# POWER.net
KiCad netlist of a schematic drawn in Altium Designer
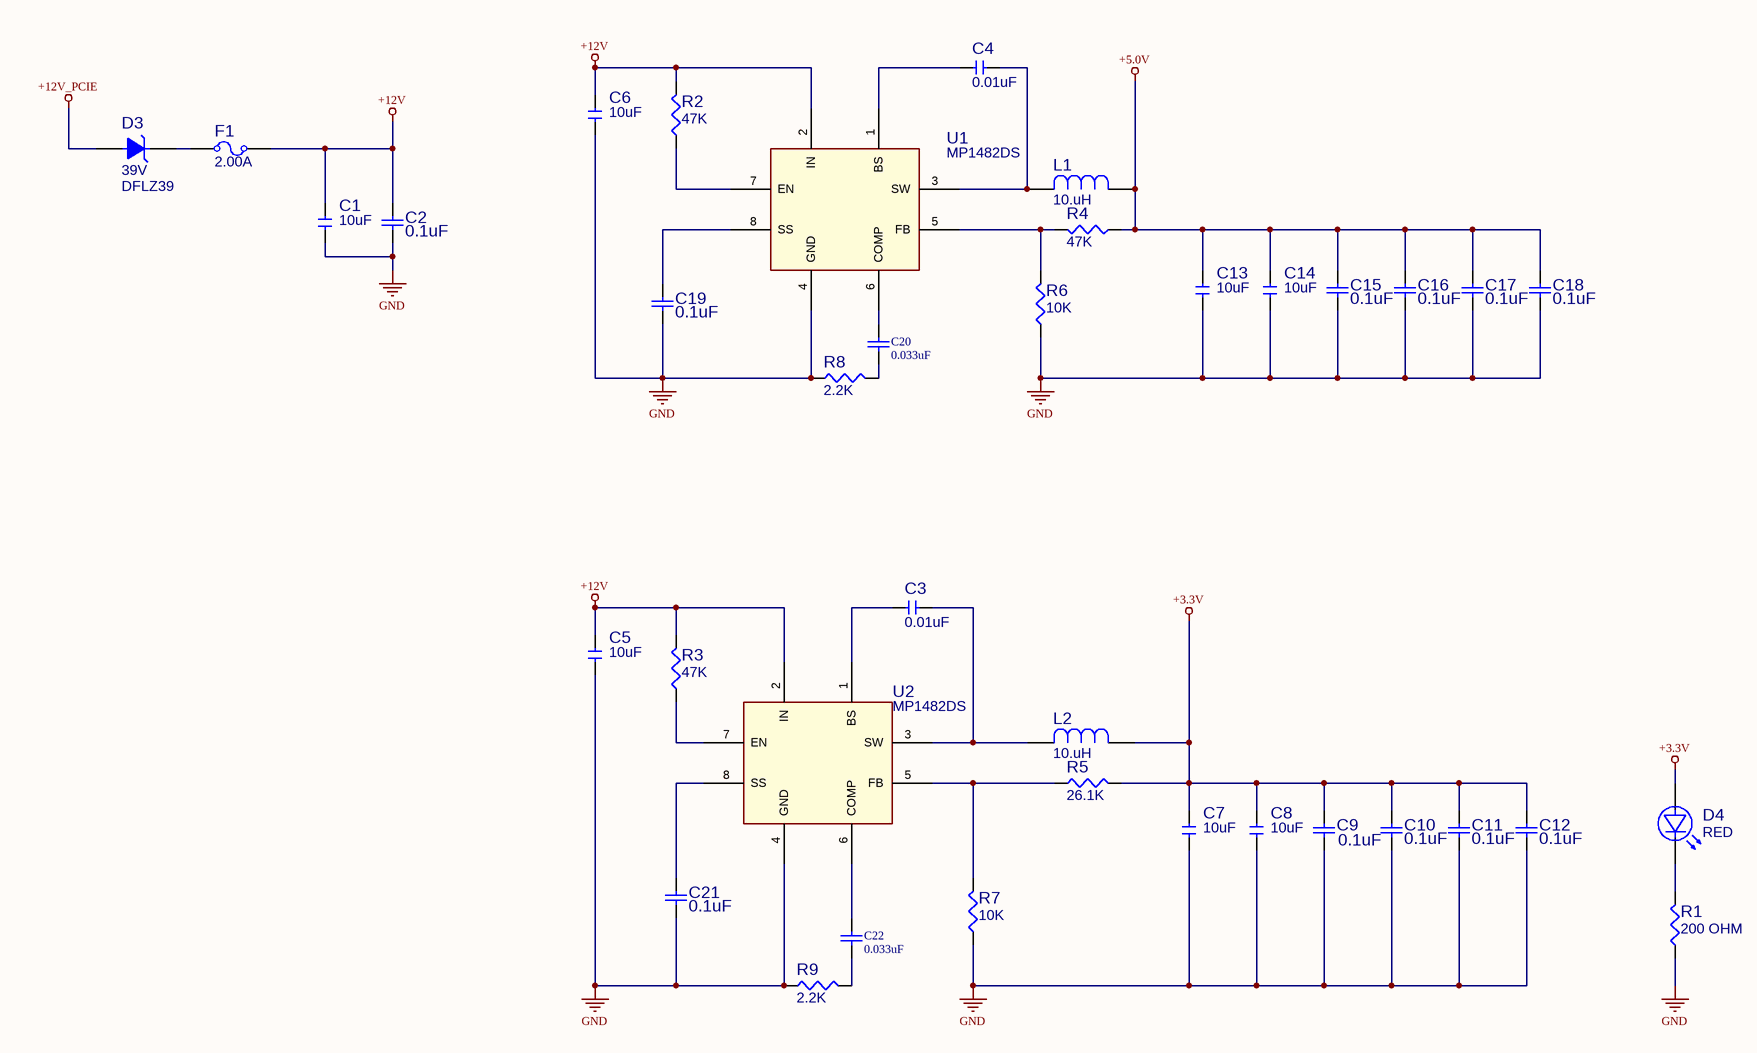
[diagram p0: POWER.SchDoc]

(export (version "E")
  (design (tool "Eeschema 10.0.6"))
  (components
    (comp (ref "C1")
      (value "10uF")
      (footprint "CAPC2012X14N")
      (description "CAP, CER, 10.UF, 25V, 10%, X5R, 0805")
      (fields
        (field (name "MFG PART NUM") "TMK212BBJ106KG-T")
        (field (name "VALENTIUM PART NUM") "<VALENTIUM>")
      )
      (libsource (lib "Capacitors") (part "CAP_0805_10UF_25V"))
    )
    (comp (ref "C2")
      (value "0.1uF")
      (footprint "CAPC1608X87X45ML20T05")
      (description "C0603X104K5RACAUTO")
      (fields (field (name "MANUFACTURER") "Kemet"))
      (libsource (lib "Altium Content Vault") (part "CAP"))
    )
    (comp (ref "C3")
      (value "0.01uF")
      (footprint "CAPC1608X10N")
      (description "CAP, CER, 0.01UF, 50V, 10%, X7R, 0603")
      (fields
        (field (name "MFG PART NUM") "C0603C103K5RACTU")
        (field (name "VALENTIUM PART NUM") "<VALENTIUM>")
      )
      (libsource (lib "Capacitors") (part "CAP_0603_0.01UF_50V"))
    )
    (comp (ref "C4")
      (value "0.01uF")
      (footprint "CAPC1608X10N")
      (description "CAP, CER, 0.01UF, 50V, 10%, X7R, 0603")
      (fields
        (field (name "MFG PART NUM") "C0603C103K5RACTU")
        (field (name "VALENTIUM PART NUM") "<VALENTIUM>")
      )
      (libsource (lib "Capacitors") (part "CAP_0603_0.01UF_50V"))
    )
    (comp (ref "C5")
      (value "10uF")
      (footprint "CAPC2012X14N")
      (description "CAP, CER, 10.UF, 25V, 10%, X5R, 0805")
      (fields
        (field (name "MFG PART NUM") "TMK212BBJ106KG-T")
        (field (name "VALENTIUM PART NUM") "<VALENTIUM>")
      )
      (libsource (lib "Capacitors") (part "CAP_0805_10UF_25V"))
    )
    (comp (ref "C6")
      (value "10uF")
      (footprint "CAPC2012X14N")
      (description "CAP, CER, 10.UF, 25V, 10%, X5R, 0805")
      (fields
        (field (name "MFG PART NUM") "TMK212BBJ106KG-T")
        (field (name "VALENTIUM PART NUM") "<VALENTIUM>")
      )
      (libsource (lib "Capacitors") (part "CAP_0805_10UF_25V"))
    )
    (comp (ref "C7")
      (value "10uF")
      (footprint "CAPC2012X14N")
      (description "CAP, CER, 10.UF, 25V, 10%, X5R, 0805")
      (fields
        (field (name "MFG PART NUM") "TMK212BBJ106KG-T")
        (field (name "VALENTIUM PART NUM") "<VALENTIUM>")
      )
      (libsource (lib "Capacitors") (part "CAP_0805_10UF_25V"))
    )
    (comp (ref "C8")
      (value "10uF")
      (footprint "CAPC2012X14N")
      (description "CAP, CER, 10.UF, 25V, 10%, X5R, 0805")
      (fields
        (field (name "MFG PART NUM") "TMK212BBJ106KG-T")
        (field (name "VALENTIUM PART NUM") "<VALENTIUM>")
      )
      (libsource (lib "Capacitors") (part "CAP_0805_10UF_25V"))
    )
    (comp (ref "C9")
      (value "0.1uF")
      (footprint "CAPC1608X87X45ML20T05")
      (description "C0603X104K5RACAUTO")
      (fields (field (name "MANUFACTURER") "Kemet"))
      (libsource (lib "Altium Content Vault") (part "CAP"))
    )
    (comp (ref "C10")
      (value "0.1uF")
      (footprint "CAPC1608X87X45ML20T05")
      (description "C0603X104K5RACAUTO")
      (fields (field (name "MANUFACTURER") "Kemet"))
      (libsource (lib "Altium Content Vault") (part "CAP"))
    )
    (comp (ref "C11")
      (value "0.1uF")
      (footprint "CAPC1608X87X45ML20T05")
      (description "C0603X104K5RACAUTO")
      (fields (field (name "MANUFACTURER") "Kemet"))
      (libsource (lib "Altium Content Vault") (part "CAP"))
    )
    (comp (ref "C12")
      (value "0.1uF")
      (footprint "CAPC1608X87X45ML20T05")
      (description "C0603X104K5RACAUTO")
      (fields (field (name "MANUFACTURER") "Kemet"))
      (libsource (lib "Altium Content Vault") (part "CAP"))
    )
    (comp (ref "C13")
      (value "10uF")
      (footprint "CAPC2012X14N")
      (description "CAP, CER, 10.UF, 25V, 10%, X5R, 0805")
      (fields
        (field (name "MFG PART NUM") "TMK212BBJ106KG-T")
        (field (name "VALENTIUM PART NUM") "<VALENTIUM>")
      )
      (libsource (lib "Capacitors") (part "CAP_0805_10UF_25V"))
    )
    (comp (ref "C14")
      (value "10uF")
      (footprint "CAPC2012X14N")
      (description "CAP, CER, 10.UF, 25V, 10%, X5R, 0805")
      (fields
        (field (name "MFG PART NUM") "TMK212BBJ106KG-T")
        (field (name "VALENTIUM PART NUM") "<VALENTIUM>")
      )
      (libsource (lib "Capacitors") (part "CAP_0805_10UF_25V"))
    )
    (comp (ref "C15")
      (value "0.1uF")
      (footprint "CAPC1608X87X45ML20T05")
      (description "C0603X104K5RACAUTO")
      (fields (field (name "MANUFACTURER") "Kemet"))
      (libsource (lib "Altium Content Vault") (part "CAP"))
    )
    (comp (ref "C16")
      (value "0.1uF")
      (footprint "CAPC1608X87X45ML20T05")
      (description "C0603X104K5RACAUTO")
      (fields (field (name "MANUFACTURER") "Kemet"))
      (libsource (lib "Altium Content Vault") (part "CAP"))
    )
    (comp (ref "C17")
      (value "0.1uF")
      (footprint "CAPC1608X87X45ML20T05")
      (description "C0603X104K5RACAUTO")
      (fields (field (name "MANUFACTURER") "Kemet"))
      (libsource (lib "Altium Content Vault") (part "CAP"))
    )
    (comp (ref "C18")
      (value "0.1uF")
      (footprint "CAPC1608X87X45ML20T05")
      (description "C0603X104K5RACAUTO")
      (fields (field (name "MANUFACTURER") "Kemet"))
      (libsource (lib "Altium Content Vault") (part "CAP"))
    )
    (comp (ref "C19")
      (value "0.1uF")
      (footprint "CAPC1608X87X45ML20T05")
      (description "C0603X104K5RACAUTO")
      (fields (field (name "MANUFACTURER") "Kemet"))
      (libsource (lib "Altium Content Vault") (part "CAP"))
    )
    (comp (ref "C20")
      (value "0.033uF")
      (footprint "CAPC1608X90X35NL10T15")
      (description "GCM188R71H333KA55D")
      (fields (field (name "MANUFACTURER") "Murata"))
      (libsource (lib "Altium Content Vault") (part "CAP"))
    )
    (comp (ref "C21")
      (value "0.1uF")
      (footprint "CAPC1608X87X45ML20T05")
      (description "C0603X104K5RACAUTO")
      (fields (field (name "MANUFACTURER") "Kemet"))
      (libsource (lib "Altium Content Vault") (part "CAP"))
    )
    (comp (ref "C22")
      (value "0.033uF")
      (footprint "CAPC1608X90X35NL10T15")
      (description "GCM188R71H333KA55D")
      (fields (field (name "MANUFACTURER") "Murata"))
      (libsource (lib "Altium Content Vault") (part "CAP"))
    )
    (comp (ref "D3")
      (value "DFLZ39")
      (footprint "SODFL370X135-2N")
      (description "DIO, ZENER, DFLZ39, 39V, 5%, 1W, SOD123FL")
      (fields
        (field (name "MFG PART NUM") "DFLZ39-TP")
        (field (name "P1") "39V")
        (field (name "VALENTIUM PART NUM") "<VALENTIUM>")
      )
      (libsource (lib "Passives") (part "DFLZ39"))
    )
    (comp (ref "D4")
      (value "RED")
      (footprint "DIOM1608X06N")
      (description "LED, RED, SML-LX0603, 635NM, 2V, 20MA, 0603")
      (fields
        (field (name "MFG PART NUM") "SML-LX0603IW-TR")
        (field (name "VALENTIUM PART NUM") "<VALENTIUM>")
      )
      (libsource (lib "Passives") (part "SMTLED_RED_0603_SML"))
    )
    (comp (ref "F1")
      (value "2.00A")
      (footprint "FUSM1608X60N")
      (description "FUSE SLOW 2.00A 32V M 0603")
      (fields (field (name "MFG PART NUM") "SF-0603S200-2") (field (name "VALENTIUM PART NUM") "<VALENTIUM>"))
      (libsource (lib "Passives") (part "FUSE_0603_2.00A"))
    )
    (comp (ref "L1")
      (value "10.uH")
      (footprint "IND_PM124SH")
      (description "IND, PWR, 10.uH, 20%, 4A, 0.04DCR, 12.5X12.5MM, SHLD")
      (fields
        (field (name "MFG PART NUM") "PM124SH-100M-RC")
        (field (name "VALENTIUM PART NUM") "<VALENTIUM>")
      )
      (libsource (lib "Passives") (part "PM124SH-100M-RC"))
    )
    (comp (ref "L2")
      (value "10.uH")
      (footprint "IND_PM124SH")
      (description "IND, PWR, 10.uH, 20%, 4A, 0.04DCR, 12.5X12.5MM, SHLD")
      (fields
        (field (name "MFG PART NUM") "PM124SH-100M-RC")
        (field (name "VALENTIUM PART NUM") "<VALENTIUM>")
      )
      (libsource (lib "Passives") (part "PM124SH-100M-RC"))
    )
    (comp (ref "R1")
      (value "200 OHM")
      (footprint "RESC1608X50N")
      (description "RES, 200 OHM, 1%, 1/10W, TF, 0603")
      (fields (field (name "MFG PART NUM") "ERJ-3EKF2000V") (field (name "VELENTIUM PART NUM") "<VELENTIUM>"))
      (libsource (lib "Resistors") (part "RES_0603_200"))
    )
    (comp (ref "R2")
      (value "47K")
      (footprint "RESC1608X50N")
      (description "RES, 47K, 1%, 1/10W, TF, 0603")
      (fields (field (name "MFG PART NUM") "ERJ-3EKF4702V") (field (name "VELENTIUM PART NUM") "<VELENTIUM>"))
      (libsource (lib "Resistors") (part "RES_0603_47K"))
    )
    (comp (ref "R3")
      (value "47K")
      (footprint "RESC1608X50N")
      (description "RES, 47K, 1%, 1/10W, TF, 0603")
      (fields (field (name "MFG PART NUM") "ERJ-3EKF4702V") (field (name "VELENTIUM PART NUM") "<VELENTIUM>"))
      (libsource (lib "Resistors") (part "RES_0603_47K"))
    )
    (comp (ref "R4")
      (value "47K")
      (footprint "RESC1608X50N")
      (description "RES, 47K, 1%, 1/10W, TF, 0603")
      (fields (field (name "MFG PART NUM") "ERJ-3EKF4702V") (field (name "VELENTIUM PART NUM") "<VELENTIUM>"))
      (libsource (lib "Resistors") (part "RES_0603_47K"))
    )
    (comp (ref "R5")
      (value "26.1K")
      (footprint "RESC1608X50N")
      (description "RES, 26.1K, 1%, 1/10W, TF, 0603")
      (fields (field (name "MFG PART NUM") "ERJ-3EKF2612V") (field (name "VELENTIUM PART NUM") "<VELENTIUM>"))
      (libsource (lib "Resistors") (part "RES_0603_26.1K"))
    )
    (comp (ref "R6")
      (value "10K")
      (footprint "RESC1608X50N")
      (description "RES, 10K, 1%, 1/10W, TF, 0603")
      (fields (field (name "MFG PART NUM") "ERJ-3EKF1002V") (field (name "VELENTIUM PART NUM") "<VELENTIUM>"))
      (libsource (lib "Resistors") (part "RES_0603_10K"))
    )
    (comp (ref "R7")
      (value "10K")
      (footprint "RESC1608X50N")
      (description "RES, 10K, 1%, 1/10W, TF, 0603")
      (fields (field (name "MFG PART NUM") "ERJ-3EKF1002V") (field (name "VELENTIUM PART NUM") "<VELENTIUM>"))
      (libsource (lib "Resistors") (part "RES_0603_10K"))
    )
    (comp (ref "R8")
      (value "2.2K")
      (footprint "RESC1608X50N")
      (description "RES, 2.2K, 1%, 1/10W, TF, 0603")
      (fields (field (name "MFG PART NUM") "ERJ-3EKF2201V") (field (name "VELENTIUM PART NUM") "<VELENTIUM>"))
      (libsource (lib "Resistors") (part "RES_0603_2.2K"))
    )
    (comp (ref "R9")
      (value "2.2K")
      (footprint "RESC1608X50N")
      (description "RES, 2.2K, 1%, 1/10W, TF, 0603")
      (fields (field (name "MFG PART NUM") "ERJ-3EKF2201V") (field (name "VELENTIUM PART NUM") "<VELENTIUM>"))
      (libsource (lib "Resistors") (part "RES_0603_2.2K"))
    )
    (comp (ref "U1")
      (value "MP1482DS")
      (footprint "SOIC127P600X175-8N")
      (description "IC, DC/DC, MP1482DS, >4.75VIN, 0.923-15V OUT, SOIC8")
      (fields (field (name "MFG PART NUM") "MP1482DS-LF") (field (name "VELENTIUM PART NUM") "<V PART NUM>"))
      (libsource (lib "IntegratedCircuits") (part "MP1482DS"))
    )
    (comp (ref "U2")
      (value "MP1482DS")
      (footprint "SOIC127P600X175-8N")
      (description "IC, DC/DC, MP1482DS, >4.75VIN, 0.923-15V OUT, SOIC8")
      (fields (field (name "MFG PART NUM") "MP1482DS-LF") (field (name "VELENTIUM PART NUM") "<V PART NUM>"))
      (libsource (lib "IntegratedCircuits") (part "MP1482DS"))
    )
  )
  (nets
    (net (code "1") (name "+3.3V") (class "Default")
      (node (ref "C10") (pin "2") (pinfunction "2_2") (pintype "passive"))
      (node (ref "C11") (pin "2") (pinfunction "2_2") (pintype "passive"))
      (node (ref "C12") (pin "2") (pinfunction "2_2") (pintype "passive"))
      (node (ref "C7") (pin "1") (pinfunction "1_1") (pintype "passive"))
      (node (ref "C8") (pin "1") (pinfunction "1_1") (pintype "passive"))
      (node (ref "C9") (pin "2") (pinfunction "2_2") (pintype "passive"))
      (node (ref "D4") (pin "2") (pinfunction "A_2") (pintype "passive"))
      (node (ref "L2") (pin "1") (pintype "passive"))
      (node (ref "R5") (pin "2") (pinfunction "2_2") (pintype "passive"))
    )
    (net (code "2") (name "+5.0V") (class "Default")
      (node (ref "C13") (pin "1") (pinfunction "1_1") (pintype "passive"))
      (node (ref "C14") (pin "1") (pinfunction "1_1") (pintype "passive"))
      (node (ref "C15") (pin "2") (pinfunction "2_2") (pintype "passive"))
      (node (ref "C16") (pin "2") (pinfunction "2_2") (pintype "passive"))
      (node (ref "C17") (pin "2") (pinfunction "2_2") (pintype "passive"))
      (node (ref "C18") (pin "2") (pinfunction "2_2") (pintype "passive"))
      (node (ref "L1") (pin "1") (pintype "passive"))
      (node (ref "R4") (pin "1") (pinfunction "1_1") (pintype "passive"))
    )
    (net (code "3") (name "+12V") (class "Default")
      (node (ref "C1") (pin "1") (pinfunction "1_1") (pintype "passive"))
      (node (ref "C2") (pin "2") (pinfunction "2_2") (pintype "passive"))
      (node (ref "C5") (pin "1") (pinfunction "1_1") (pintype "passive"))
      (node (ref "C6") (pin "1") (pinfunction "1_1") (pintype "passive"))
      (node (ref "F1") (pin "2") (pinfunction "2_2") (pintype "passive"))
      (node (ref "R2") (pin "2") (pinfunction "2_2") (pintype "passive"))
      (node (ref "R3") (pin "2") (pinfunction "2_2") (pintype "passive"))
      (node (ref "U1") (pin "2") (pinfunction "IN_2") (pintype "passive"))
      (node (ref "U2") (pin "2") (pinfunction "IN_2") (pintype "passive"))
    )
    (net (code "4") (name "+12V_PCIE") (class "Default")
      (node (ref "D3") (pin "2") (pinfunction "A_2") (pintype "passive"))
    )
    (net (code "5") (name "GND") (class "Default")
      (node (ref "C1") (pin "2") (pinfunction "2_2") (pintype "passive"))
      (node (ref "C10") (pin "1") (pinfunction "1_1") (pintype "passive"))
      (node (ref "C11") (pin "1") (pinfunction "1_1") (pintype "passive"))
      (node (ref "C12") (pin "1") (pinfunction "1_1") (pintype "passive"))
      (node (ref "C13") (pin "2") (pinfunction "2_2") (pintype "passive"))
      (node (ref "C14") (pin "2") (pinfunction "2_2") (pintype "passive"))
      (node (ref "C15") (pin "1") (pinfunction "1_1") (pintype "passive"))
      (node (ref "C16") (pin "1") (pinfunction "1_1") (pintype "passive"))
      (node (ref "C17") (pin "1") (pinfunction "1_1") (pintype "passive"))
      (node (ref "C18") (pin "1") (pinfunction "1_1") (pintype "passive"))
      (node (ref "C19") (pin "1") (pinfunction "1_1") (pintype "passive"))
      (node (ref "C2") (pin "1") (pinfunction "1_1") (pintype "passive"))
      (node (ref "C21") (pin "1") (pinfunction "1_1") (pintype "passive"))
      (node (ref "C5") (pin "2") (pinfunction "2_2") (pintype "passive"))
      (node (ref "C6") (pin "2") (pinfunction "2_2") (pintype "passive"))
      (node (ref "C7") (pin "2") (pinfunction "2_2") (pintype "passive"))
      (node (ref "C8") (pin "2") (pinfunction "2_2") (pintype "passive"))
      (node (ref "C9") (pin "1") (pinfunction "1_1") (pintype "passive"))
      (node (ref "R1") (pin "1") (pinfunction "1_1") (pintype "passive"))
      (node (ref "R6") (pin "1") (pinfunction "1_1") (pintype "passive"))
      (node (ref "R7") (pin "1") (pinfunction "1_1") (pintype "passive"))
      (node (ref "R8") (pin "1") (pinfunction "1_1") (pintype "passive"))
      (node (ref "R9") (pin "1") (pinfunction "1_1") (pintype "passive"))
      (node (ref "U1") (pin "4") (pinfunction "GND_4") (pintype "passive"))
      (node (ref "U2") (pin "4") (pinfunction "GND_4") (pintype "passive"))
    )
    (net (code "6") (name "Net-(C20-Pad1)") (class "Default")
      (node (ref "C20") (pin "1") (pinfunction "1_1") (pintype "passive"))
      (node (ref "R8") (pin "2") (pinfunction "2_2") (pintype "passive"))
    )
    (net (code "7") (name "Net-(C22-Pad1)") (class "Default")
      (node (ref "C22") (pin "1") (pinfunction "1_1") (pintype "passive"))
      (node (ref "R9") (pin "2") (pinfunction "2_2") (pintype "passive"))
    )
    (net (code "8") (name "Net-(D3-C)") (class "Default")
      (node (ref "D3") (pin "1") (pinfunction "C_1") (pintype "passive"))
      (node (ref "F1") (pin "1") (pinfunction "1_1") (pintype "passive"))
    )
    (net (code "9") (name "Net-(D4-K)") (class "Default")
      (node (ref "D4") (pin "1") (pinfunction "K_1") (pintype "passive"))
      (node (ref "R1") (pin "2") (pinfunction "2_2") (pintype "passive"))
    )
    (net (code "10") (name "Net-(U1-BS)") (class "Default")
      (node (ref "C4") (pin "1") (pinfunction "1_1") (pintype "passive"))
      (node (ref "U1") (pin "1") (pinfunction "BS_1") (pintype "passive"))
    )
    (net (code "11") (name "Net-(U1-COMP)") (class "Default")
      (node (ref "C20") (pin "2") (pinfunction "2_2") (pintype "passive"))
      (node (ref "U1") (pin "6") (pinfunction "COMP_6") (pintype "passive"))
    )
    (net (code "12") (name "Net-(U1-EN)") (class "Default")
      (node (ref "R2") (pin "1") (pinfunction "1_1") (pintype "passive"))
      (node (ref "U1") (pin "7") (pinfunction "EN_7") (pintype "passive"))
    )
    (net (code "13") (name "Net-(U1-FB)") (class "Default")
      (node (ref "R4") (pin "2") (pinfunction "2_2") (pintype "passive"))
      (node (ref "R6") (pin "2") (pinfunction "2_2") (pintype "passive"))
      (node (ref "U1") (pin "5") (pinfunction "FB_5") (pintype "passive"))
    )
    (net (code "14") (name "Net-(U1-SS)") (class "Default")
      (node (ref "C19") (pin "2") (pinfunction "2_2") (pintype "passive"))
      (node (ref "U1") (pin "8") (pinfunction "SS_8") (pintype "passive"))
    )
    (net (code "15") (name "Net-(U1-SW)") (class "Default")
      (node (ref "C4") (pin "2") (pinfunction "2_2") (pintype "passive"))
      (node (ref "L1") (pin "2") (pintype "passive"))
      (node (ref "U1") (pin "3") (pinfunction "SW_3") (pintype "passive"))
    )
    (net (code "16") (name "Net-(U2-BS)") (class "Default")
      (node (ref "C3") (pin "1") (pinfunction "1_1") (pintype "passive"))
      (node (ref "U2") (pin "1") (pinfunction "BS_1") (pintype "passive"))
    )
    (net (code "17") (name "Net-(U2-COMP)") (class "Default")
      (node (ref "C22") (pin "2") (pinfunction "2_2") (pintype "passive"))
      (node (ref "U2") (pin "6") (pinfunction "COMP_6") (pintype "passive"))
    )
    (net (code "18") (name "Net-(U2-EN)") (class "Default")
      (node (ref "R3") (pin "1") (pinfunction "1_1") (pintype "passive"))
      (node (ref "U2") (pin "7") (pinfunction "EN_7") (pintype "passive"))
    )
    (net (code "19") (name "Net-(U2-FB)") (class "Default")
      (node (ref "R5") (pin "1") (pinfunction "1_1") (pintype "passive"))
      (node (ref "R7") (pin "2") (pinfunction "2_2") (pintype "passive"))
      (node (ref "U2") (pin "5") (pinfunction "FB_5") (pintype "passive"))
    )
    (net (code "20") (name "Net-(U2-SS)") (class "Default")
      (node (ref "C21") (pin "2") (pinfunction "2_2") (pintype "passive"))
      (node (ref "U2") (pin "8") (pinfunction "SS_8") (pintype "passive"))
    )
    (net (code "21") (name "Net-(U2-SW)") (class "Default")
      (node (ref "C3") (pin "2") (pinfunction "2_2") (pintype "passive"))
      (node (ref "L2") (pin "2") (pintype "passive"))
      (node (ref "U2") (pin "3") (pinfunction "SW_3") (pintype "passive"))
    )
  )
)
